# Arduino_EG.net
KiCad netlist of a schematic drawn in EAGLE
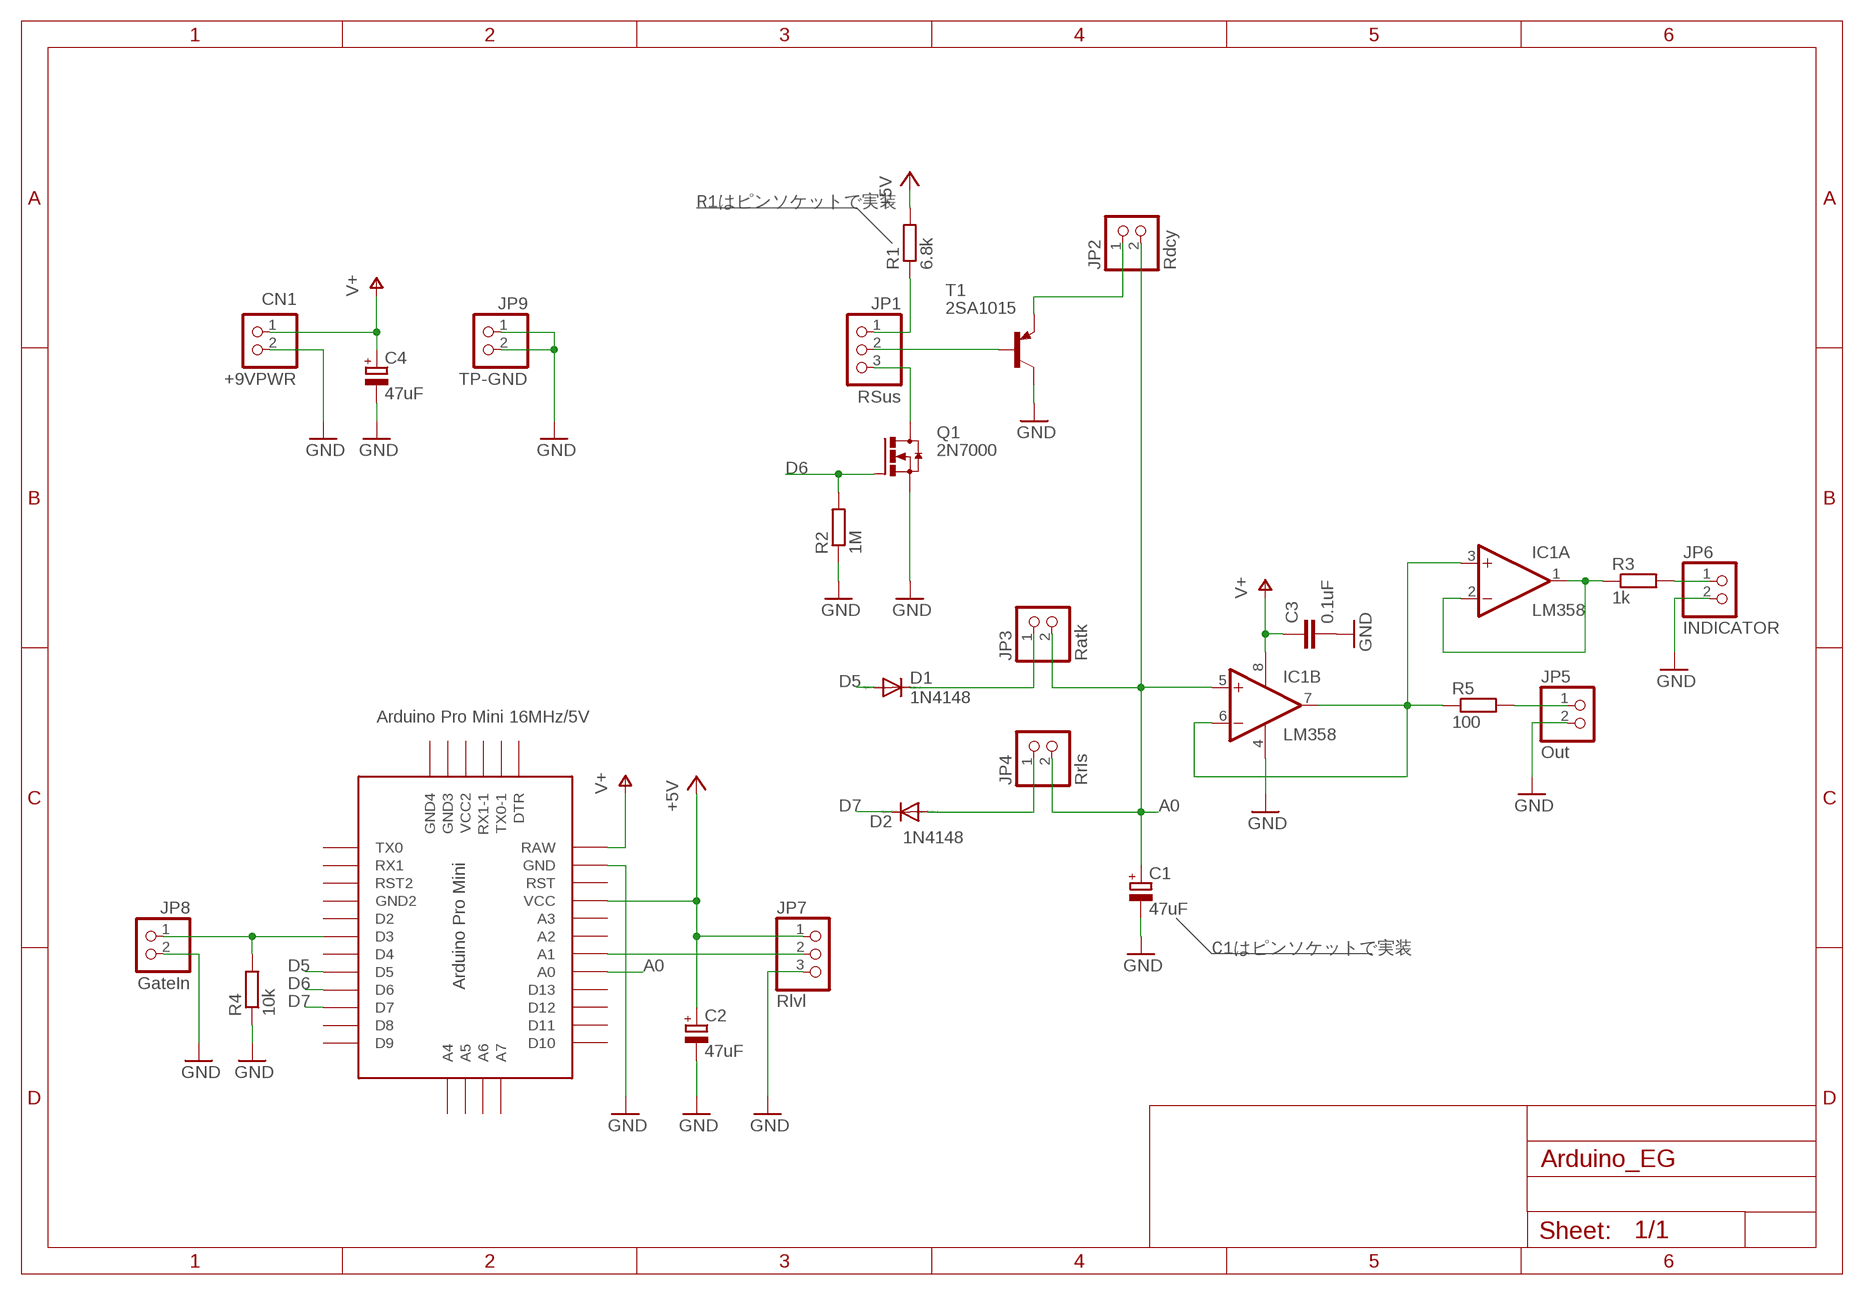
[diagram p0: schematic, sheet 1]

(export (version "E")
  (design (tool "Eeschema 10.0.6"))
  (components
    (comp (ref "C1")
      (value "47uF")
      (footprint "eagle-import:E2,5-7")
      (libsource (lib "eagle-import") (part "CPOL-EUE2.5-7"))
    )
    (comp (ref "C2")
      (value "47uF")
      (footprint "eagle-import:E2,5-7")
      (libsource (lib "eagle-import") (part "CPOL-EUE2.5-7"))
    )
    (comp (ref "C3")
      (value "0.1uF")
      (footprint "eagle-import:C025-025X050")
      (libsource (lib "eagle-import") (part "C-EU025-025X050"))
    )
    (comp (ref "C4")
      (value "47uF")
      (footprint "eagle-import:E2,5-7")
      (libsource (lib "eagle-import") (part "CPOL-EUE2.5-7"))
    )
    (comp (ref "CN1")
      (value "+9VPWR")
      (footprint "eagle-import:B2B-XH-A")
      (libsource (lib "eagle-import") (part "B2B-XH-A"))
    )
    (comp (ref "D1")
      (value "1N4148")
      (footprint "eagle-import:DO35-7")
      (libsource (lib "eagle-import") (part "1N4148DO35-7"))
    )
    (comp (ref "D2")
      (value "1N4148")
      (footprint "eagle-import:DO35-7")
      (libsource (lib "eagle-import") (part "1N4148DO35-7"))
    )
    (comp (ref "IC1")
      (value "LM358")
      (footprint "eagle-import:DIL08")
      (libsource (lib "eagle-import") (part "LM358N"))
    )
    (comp (ref "JP1")
      (value "RSus")
      (footprint "eagle-import:1X03")
      (libsource (lib "eagle-import") (part "PINHD-1X3"))
    )
    (comp (ref "JP2")
      (value "Rdcy")
      (footprint "eagle-import:1X02")
      (libsource (lib "eagle-import") (part "PINHD-1X2"))
    )
    (comp (ref "JP3")
      (value "Ratk")
      (footprint "eagle-import:1X02")
      (libsource (lib "eagle-import") (part "PINHD-1X2"))
    )
    (comp (ref "JP4")
      (value "Rrls")
      (footprint "eagle-import:1X02")
      (libsource (lib "eagle-import") (part "PINHD-1X2"))
    )
    (comp (ref "JP5")
      (value "Out")
      (footprint "eagle-import:1X02")
      (libsource (lib "eagle-import") (part "PINHD-1X2"))
    )
    (comp (ref "JP6")
      (value "INDICATOR")
      (footprint "eagle-import:1X02")
      (libsource (lib "eagle-import") (part "PINHD-1X2"))
    )
    (comp (ref "JP7")
      (value "Rlvl")
      (footprint "eagle-import:1X03")
      (libsource (lib "eagle-import") (part "PINHD-1X3"))
    )
    (comp (ref "JP8")
      (value "GateIn")
      (footprint "eagle-import:1X02")
      (libsource (lib "eagle-import") (part "PINHD-1X2"))
    )
    (comp (ref "JP9")
      (value "TP-GND")
      (footprint "eagle-import:1X02")
      (libsource (lib "eagle-import") (part "PINHD-1X2"))
    )
    (comp (ref "Q1")
      (value "2N7000")
      (footprint "eagle-import:TO92-")
      (libsource (lib "eagle-import") (part "2N7000"))
    )
    (comp (ref "R1")
      (value "6.8k")
      (footprint "eagle-import:0207_7")
      (libsource (lib "eagle-import") (part "R-EU_0207/7"))
    )
    (comp (ref "R2")
      (value "1M")
      (footprint "eagle-import:0207_7")
      (libsource (lib "eagle-import") (part "R-EU_0207/7"))
    )
    (comp (ref "R3")
      (value "1k")
      (footprint "eagle-import:0207_7")
      (libsource (lib "eagle-import") (part "R-EU_0207/7"))
    )
    (comp (ref "R4")
      (value "10k")
      (footprint "eagle-import:0207_7")
      (libsource (lib "eagle-import") (part "R-EU_0207/7"))
    )
    (comp (ref "R5")
      (value "100")
      (footprint "eagle-import:0207_7")
      (libsource (lib "eagle-import") (part "R-EU_0207/7"))
    )
    (comp (ref "T1")
      (value "2SA1015")
      (footprint "eagle-import:TO92-ECB")
      (libsource (lib "eagle-import") (part "-PNP-TO92-ECB"))
    )
    (comp (ref "U$1")
      (value "PRO-MINI")
      (footprint "eagle-import:PRO-MINI")
      (libsource (lib "eagle-import") (part "PRO-MINI"))
    )
  )
  (nets
    (net (code "1") (name "+5V") (class "Default")
      (node (ref "C2") (pin "+") (pinfunction "+_+") (pintype "passive"))
      (node (ref "JP7") (pin "1") (pinfunction "1_1") (pintype "passive"))
      (node (ref "R1") (pin "2") (pinfunction "2_2") (pintype "passive"))
      (node (ref "U$1") (pin "VCC") (pinfunction "VCC_VCC") (pintype "bidirectional"))
    )
    (net (code "2") (name "/A0") (class "Default")
      (node (ref "C1") (pin "+") (pinfunction "+_+") (pintype "passive"))
      (node (ref "IC1") (pin "5") (pinfunction "+IN_5") (pintype "input"))
      (node (ref "JP2") (pin "2") (pinfunction "2_2") (pintype "passive"))
      (node (ref "JP3") (pin "2") (pinfunction "2_2") (pintype "passive"))
      (node (ref "JP4") (pin "2") (pinfunction "2_2") (pintype "passive"))
      (node (ref "U$1") (pin "A0") (pinfunction "A0_A0") (pintype "bidirectional"))
    )
    (net (code "3") (name "/D5") (class "Default")
      (node (ref "D1") (pin "A") (pinfunction "A_A") (pintype "passive"))
      (node (ref "U$1") (pin "D5") (pinfunction "D5_D5") (pintype "bidirectional"))
    )
    (net (code "4") (name "/D6") (class "Default")
      (node (ref "Q1") (pin "2") (pinfunction "G_2") (pintype "passive"))
      (node (ref "R2") (pin "2") (pinfunction "2_2") (pintype "passive"))
      (node (ref "U$1") (pin "D6") (pinfunction "D6_D6") (pintype "bidirectional"))
    )
    (net (code "5") (name "/D7") (class "Default")
      (node (ref "D2") (pin "C") (pinfunction "C_C") (pintype "passive"))
      (node (ref "U$1") (pin "D7") (pinfunction "D7_D7") (pintype "bidirectional"))
    )
    (net (code "6") (name "GND") (class "Default")
      (node (ref "C1") (pin "-") (pinfunction "-_-") (pintype "passive"))
      (node (ref "C2") (pin "-") (pinfunction "-_-") (pintype "passive"))
      (node (ref "C3") (pin "2") (pinfunction "2_2") (pintype "passive"))
      (node (ref "C4") (pin "-") (pinfunction "-_-") (pintype "passive"))
      (node (ref "CN1") (pin "2") (pinfunction "2_2") (pintype "passive"))
      (node (ref "IC1") (pin "4") (pinfunction "V-_4") (pintype "power_in"))
      (node (ref "JP5") (pin "2") (pinfunction "2_2") (pintype "passive"))
      (node (ref "JP6") (pin "2") (pinfunction "2_2") (pintype "passive"))
      (node (ref "JP7") (pin "3") (pinfunction "3_3") (pintype "passive"))
      (node (ref "JP8") (pin "2") (pinfunction "2_2") (pintype "passive"))
      (node (ref "JP9") (pin "1") (pinfunction "1_1") (pintype "passive"))
      (node (ref "JP9") (pin "2") (pinfunction "2_2") (pintype "passive"))
      (node (ref "Q1") (pin "3") (pinfunction "S_3") (pintype "passive"))
      (node (ref "R2") (pin "1") (pinfunction "1_1") (pintype "passive"))
      (node (ref "R4") (pin "1") (pinfunction "1_1") (pintype "passive"))
      (node (ref "T1") (pin "C") (pinfunction "C_C") (pintype "passive"))
      (node (ref "U$1") (pin "GND") (pinfunction "GND_GND") (pintype "input"))
    )
    (net (code "7") (name "Net-(D1-PadC)") (class "Default")
      (node (ref "D1") (pin "C") (pinfunction "C_C") (pintype "passive"))
      (node (ref "JP3") (pin "1") (pinfunction "1_1") (pintype "passive"))
    )
    (net (code "8") (name "Net-(D2-PadA)") (class "Default")
      (node (ref "D2") (pin "A") (pinfunction "A_A") (pintype "passive"))
      (node (ref "JP4") (pin "1") (pinfunction "1_1") (pintype "passive"))
    )
    (net (code "9") (name "Net-(IC1A-+IN)") (class "Default")
      (node (ref "IC1") (pin "3") (pinfunction "+IN_3") (pintype "input"))
      (node (ref "IC1") (pin "6") (pinfunction "-IN_6") (pintype "input"))
      (node (ref "IC1") (pin "7") (pinfunction "OUT_7") (pintype "output"))
      (node (ref "R5") (pin "1") (pinfunction "1_1") (pintype "passive"))
    )
    (net (code "10") (name "Net-(IC1A--IN)") (class "Default")
      (node (ref "IC1") (pin "1") (pinfunction "OUT_1") (pintype "output"))
      (node (ref "IC1") (pin "2") (pinfunction "-IN_2") (pintype "input"))
      (node (ref "R3") (pin "1") (pinfunction "1_1") (pintype "passive"))
    )
    (net (code "11") (name "Net-(JP1-Pad1)") (class "Default")
      (node (ref "JP1") (pin "1") (pinfunction "1_1") (pintype "passive"))
      (node (ref "R1") (pin "1") (pinfunction "1_1") (pintype "passive"))
    )
    (net (code "12") (name "Net-(JP1-Pad2)") (class "Default")
      (node (ref "JP1") (pin "2") (pinfunction "2_2") (pintype "passive"))
      (node (ref "T1") (pin "B") (pinfunction "B_B") (pintype "passive"))
    )
    (net (code "13") (name "Net-(JP2-Pad1)") (class "Default")
      (node (ref "JP2") (pin "1") (pinfunction "1_1") (pintype "passive"))
      (node (ref "T1") (pin "E") (pinfunction "E_E") (pintype "passive"))
    )
    (net (code "14") (name "Net-(JP5-Pad1)") (class "Default")
      (node (ref "JP5") (pin "1") (pinfunction "1_1") (pintype "passive"))
      (node (ref "R5") (pin "2") (pinfunction "2_2") (pintype "passive"))
    )
    (net (code "15") (name "Net-(JP6-Pad1)") (class "Default")
      (node (ref "JP6") (pin "1") (pinfunction "1_1") (pintype "passive"))
      (node (ref "R3") (pin "2") (pinfunction "2_2") (pintype "passive"))
    )
    (net (code "16") (name "Net-(JP7-Pad2)") (class "Default")
      (node (ref "JP7") (pin "2") (pinfunction "2_2") (pintype "passive"))
      (node (ref "U$1") (pin "A1") (pinfunction "A1_A1") (pintype "bidirectional"))
    )
    (net (code "17") (name "Net-(JP8-Pad1)") (class "Default")
      (node (ref "JP8") (pin "1") (pinfunction "1_1") (pintype "passive"))
      (node (ref "R4") (pin "2") (pinfunction "2_2") (pintype "passive"))
      (node (ref "U$1") (pin "D3") (pinfunction "D3_D3") (pintype "bidirectional"))
    )
    (net (code "18") (name "Net-(Q1-D)") (class "Default")
      (node (ref "JP1") (pin "3") (pinfunction "3_3") (pintype "passive"))
      (node (ref "Q1") (pin "1") (pinfunction "D_1") (pintype "passive"))
    )
    (net (code "19") (name "V+") (class "Default")
      (node (ref "C3") (pin "1") (pinfunction "1_1") (pintype "passive"))
      (node (ref "C4") (pin "+") (pinfunction "+_+") (pintype "passive"))
      (node (ref "CN1") (pin "1") (pinfunction "1_1") (pintype "passive"))
      (node (ref "IC1") (pin "8") (pinfunction "V+_8") (pintype "power_in"))
      (node (ref "U$1") (pin "RAW") (pinfunction "RAW_RAW") (pintype "power_in"))
    )
    (net (code "20") (name "unconnected-(U$1-GND2-PadGND1)") (class "Default")
      (node (ref "U$1") (pin "GND1") (pinfunction "GND2_GND1") (pintype "bidirectional"))
    )
    (net (code "21") (name "unconnected-(U$1-GND4-PadGND2)") (class "Default")
      (node (ref "U$1") (pin "GND2") (pinfunction "GND4_GND2") (pintype "bidirectional"))
    )
    (net (code "22") (name "unconnected-(U$1-PadA2)") (class "Default")
      (node (ref "U$1") (pin "A2") (pinfunction "A2_A2") (pintype "bidirectional"))
    )
    (net (code "23") (name "unconnected-(U$1-PadA3)") (class "Default")
      (node (ref "U$1") (pin "A3") (pinfunction "A3_A3") (pintype "bidirectional"))
    )
    (net (code "24") (name "unconnected-(U$1-PadA4)") (class "Default")
      (node (ref "U$1") (pin "A4") (pinfunction "A4_A4") (pintype "bidirectional"))
    )
    (net (code "25") (name "unconnected-(U$1-PadA5)") (class "Default")
      (node (ref "U$1") (pin "A5") (pinfunction "A5_A5") (pintype "bidirectional"))
    )
    (net (code "26") (name "unconnected-(U$1-PadA6)") (class "Default")
      (node (ref "U$1") (pin "A6") (pinfunction "A6_A6") (pintype "bidirectional"))
    )
    (net (code "27") (name "unconnected-(U$1-PadA7)") (class "Default")
      (node (ref "U$1") (pin "A7") (pinfunction "A7_A7") (pintype "bidirectional"))
    )
    (net (code "28") (name "unconnected-(U$1-PadD2)") (class "Default")
      (node (ref "U$1") (pin "D2") (pinfunction "D2_D2") (pintype "bidirectional"))
    )
    (net (code "29") (name "unconnected-(U$1-PadD4)") (class "Default")
      (node (ref "U$1") (pin "D4") (pinfunction "D4_D4") (pintype "bidirectional"))
    )
    (net (code "30") (name "unconnected-(U$1-PadD8)") (class "Default")
      (node (ref "U$1") (pin "D8") (pinfunction "D8_D8") (pintype "bidirectional"))
    )
    (net (code "31") (name "unconnected-(U$1-PadD9)") (class "Default")
      (node (ref "U$1") (pin "D9") (pinfunction "D9_D9") (pintype "bidirectional"))
    )
    (net (code "32") (name "unconnected-(U$1-PadD10)") (class "Default")
      (node (ref "U$1") (pin "D10") (pinfunction "D10_D10") (pintype "bidirectional"))
    )
    (net (code "33") (name "unconnected-(U$1-PadD11)") (class "Default")
      (node (ref "U$1") (pin "D11") (pinfunction "D11_D11") (pintype "bidirectional"))
    )
    (net (code "34") (name "unconnected-(U$1-PadD12)") (class "Default")
      (node (ref "U$1") (pin "D12") (pinfunction "D12_D12") (pintype "bidirectional"))
    )
    (net (code "35") (name "unconnected-(U$1-PadD13)") (class "Default")
      (node (ref "U$1") (pin "D13") (pinfunction "D13_D13") (pintype "bidirectional"))
    )
    (net (code "36") (name "unconnected-(U$1-PadDTR)") (class "Default")
      (node (ref "U$1") (pin "DTR") (pinfunction "DTR_DTR") (pintype "bidirectional"))
    )
    (net (code "37") (name "unconnected-(U$1-PadGND3)") (class "Default")
      (node (ref "U$1") (pin "GND3") (pinfunction "GND3_GND3") (pintype "bidirectional"))
    )
    (net (code "38") (name "unconnected-(U$1-PadRST)") (class "Default")
      (node (ref "U$1") (pin "RST") (pinfunction "RST_RST") (pintype "bidirectional"))
    )
    (net (code "39") (name "unconnected-(U$1-PadRX1)") (class "Default")
      (node (ref "U$1") (pin "RX1") (pinfunction "RX1_RX1") (pintype "bidirectional"))
    )
    (net (code "40") (name "unconnected-(U$1-PadRX1-1)") (class "Default")
      (node (ref "U$1") (pin "RX1-1") (pinfunction "RX1-1_RX1-1") (pintype "bidirectional"))
    )
    (net (code "41") (name "unconnected-(U$1-PadTX0)") (class "Default")
      (node (ref "U$1") (pin "TX0") (pinfunction "TX0_TX0") (pintype "bidirectional"))
    )
    (net (code "42") (name "unconnected-(U$1-PadTX0-1)") (class "Default")
      (node (ref "U$1") (pin "TX0-1") (pinfunction "TX0-1_TX0-1") (pintype "bidirectional"))
    )
    (net (code "43") (name "unconnected-(U$1-RST2-PadRST1)") (class "Default")
      (node (ref "U$1") (pin "RST1") (pinfunction "RST2_RST1") (pintype "bidirectional"))
    )
    (net (code "44") (name "unconnected-(U$1-VCC2-PadVCC1)") (class "Default")
      (node (ref "U$1") (pin "VCC1") (pinfunction "VCC2_VCC1") (pintype "bidirectional"))
    )
  )
)
